# ENCE461TutorialSchematic.net
KiCad netlist of a schematic drawn in Altium Designer
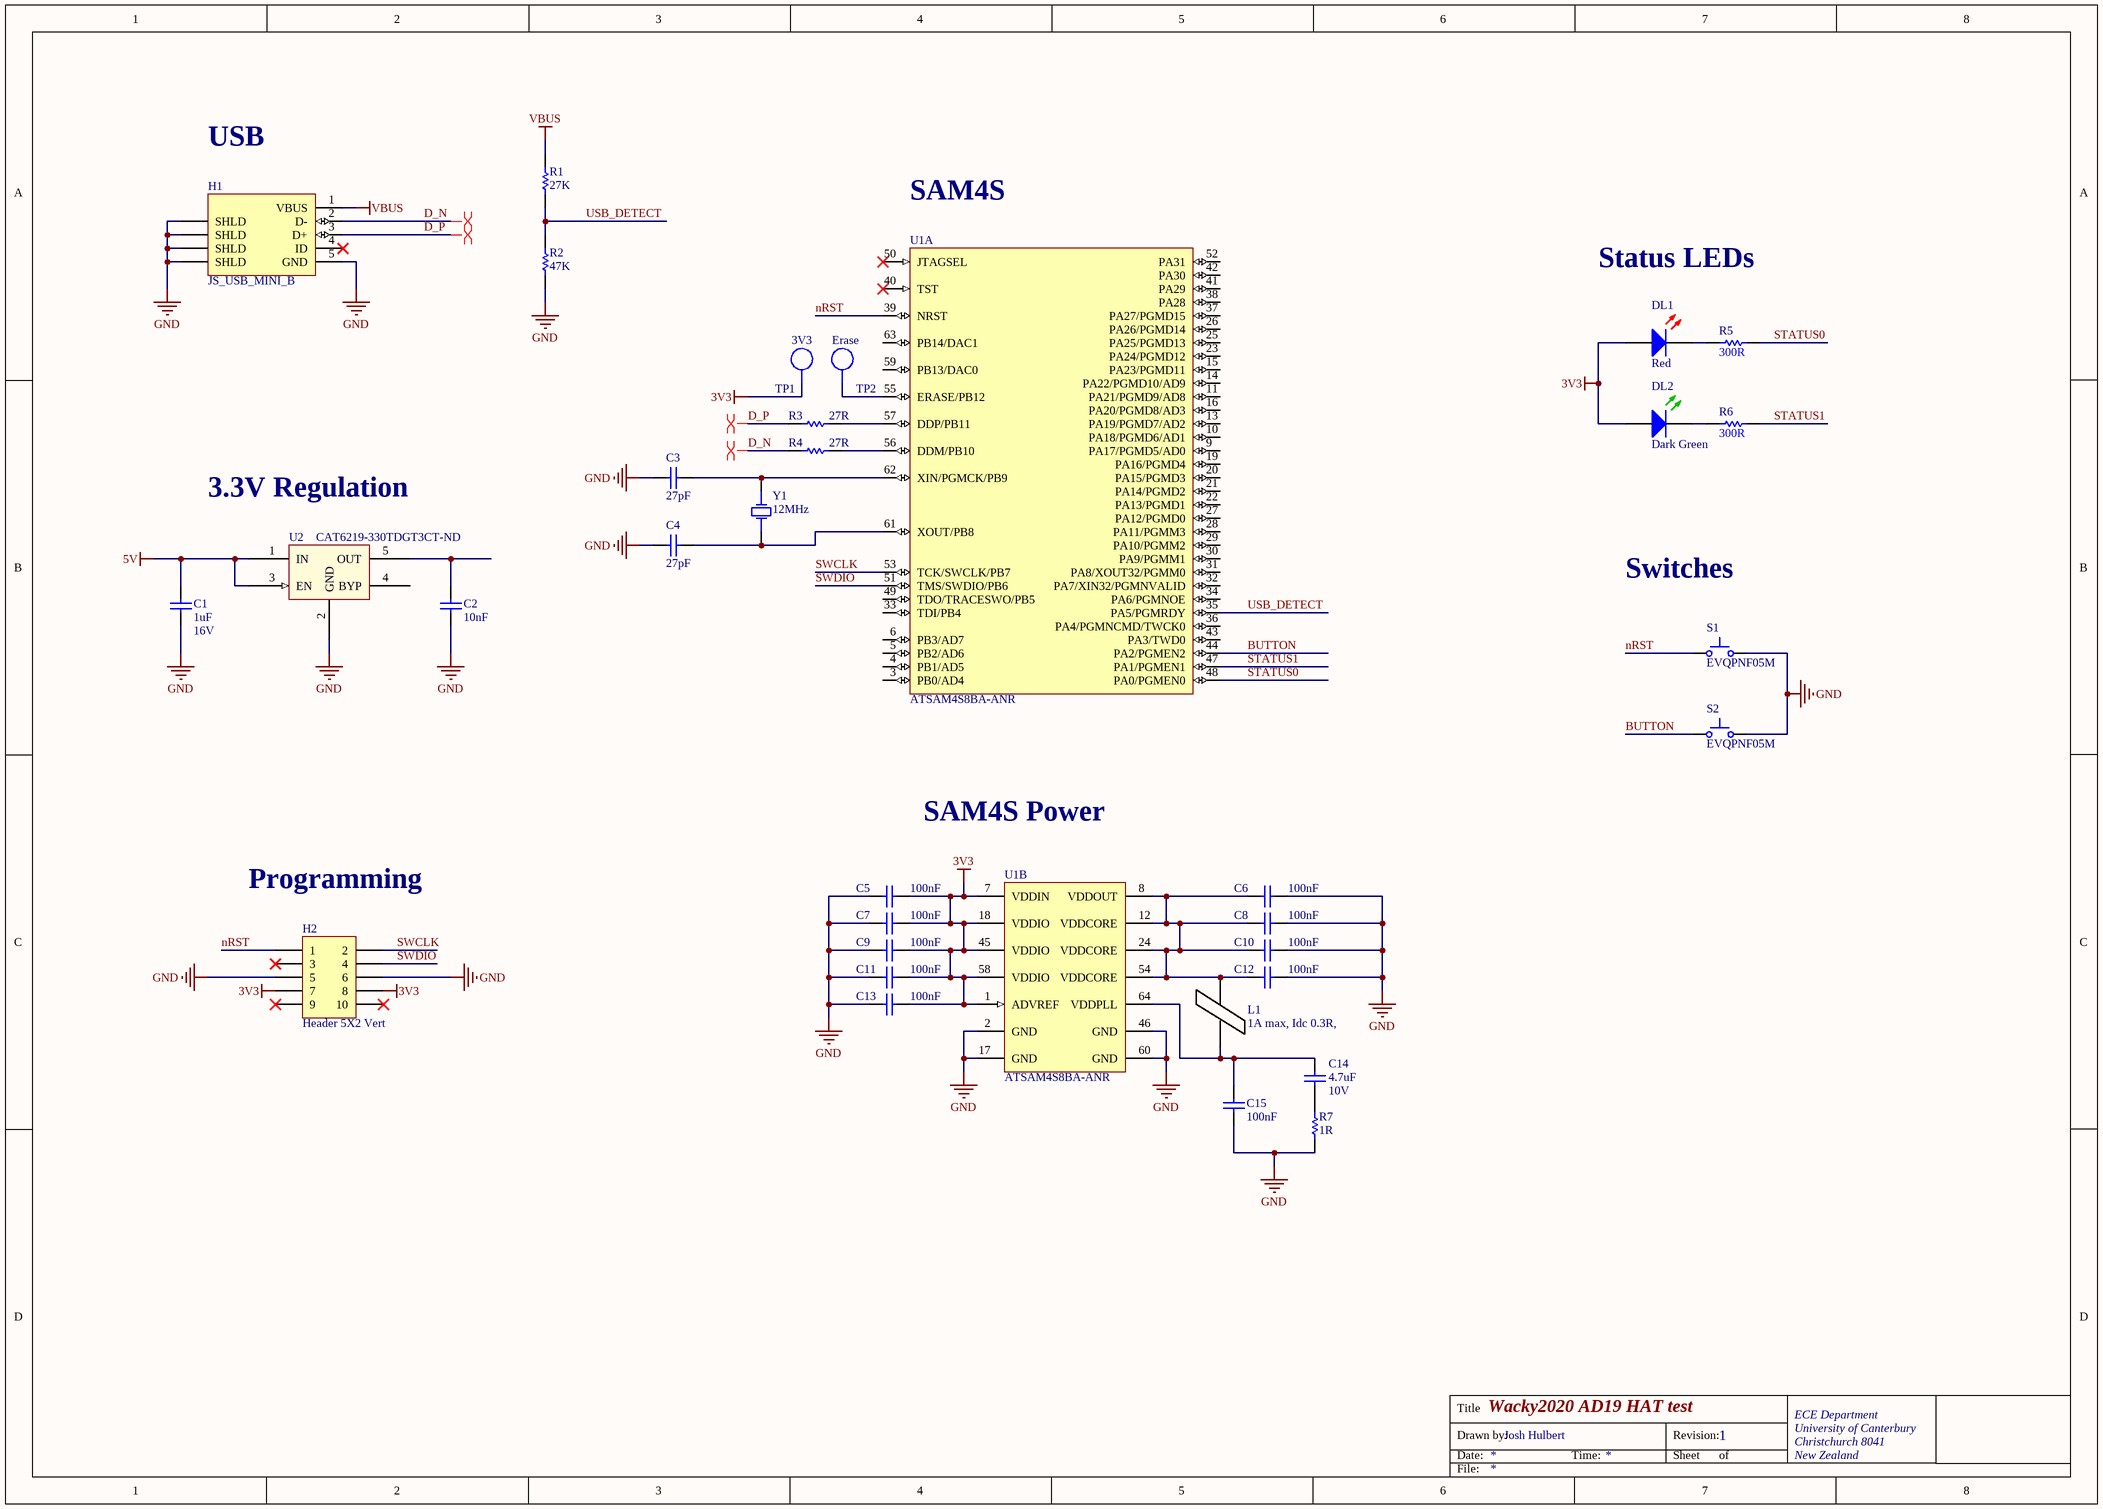
[diagram p0: ENCE461TutorialSchematic.SchDoc]

(export (version "E")
  (design (tool "Eeschema 10.0.6"))
  (components
    (comp (ref "C1")
      (value "1uF")
      (footprint "CAPC1608L")
      (description "CAP CER 1uF Y5V -20% +80% 16V 0603")
      (fields (field (name "MAX VOLTAGE") "16V"))
      (libsource (lib "ECE AD19Components_19V1") (part "CC_1uF_0603"))
    )
    (comp (ref "C2")
      (value "10nF")
      (footprint "CAPC1608L")
      (description "CAP CER 10nF X7R +-10% 50V 0603")
      (libsource (lib "ECE AD19Components_19V1") (part "CC_10nF_0603"))
    )
    (comp (ref "C3")
      (value "27pF")
      (footprint "CAPC1608L")
      (description "CAP CER 27pF NPO/COG +-5% 50V 0603")
      (libsource (lib "ECE AD19Components_19V1") (part "CC_27pF_0603"))
    )
    (comp (ref "C4")
      (value "27pF")
      (footprint "CAPC1608L")
      (description "CAP CER 27pF NPO/COG +-5% 50V 0603")
      (libsource (lib "ECE AD19Components_19V1") (part "CC_27pF_0603"))
    )
    (comp (ref "C5")
      (value "100nF")
      (footprint "CAPC1608L")
      (description "CAP CER 100nF X7R +-10% 50V 0603")
      (libsource (lib "ECE AD19Components_19V1") (part "CC_100nF_0603"))
    )
    (comp (ref "C6")
      (value "100nF")
      (footprint "CAPC1608L")
      (description "CAP CER 100nF X7R +-10% 50V 0603")
      (libsource (lib "ECE AD19Components_19V1") (part "CC_100nF_0603"))
    )
    (comp (ref "C7")
      (value "100nF")
      (footprint "CAPC1608L")
      (description "CAP CER 100nF X7R +-10% 50V 0603")
      (libsource (lib "ECE AD19Components_19V1") (part "CC_100nF_0603"))
    )
    (comp (ref "C8")
      (value "100nF")
      (footprint "CAPC1608L")
      (description "CAP CER 100nF X7R +-10% 50V 0603")
      (libsource (lib "ECE AD19Components_19V1") (part "CC_100nF_0603"))
    )
    (comp (ref "C9")
      (value "100nF")
      (footprint "CAPC1608L")
      (description "CAP CER 100nF X7R +-10% 50V 0603")
      (libsource (lib "ECE AD19Components_19V1") (part "CC_100nF_0603"))
    )
    (comp (ref "C10")
      (value "100nF")
      (footprint "CAPC1608L")
      (description "CAP CER 100nF X7R +-10% 50V 0603")
      (libsource (lib "ECE AD19Components_19V1") (part "CC_100nF_0603"))
    )
    (comp (ref "C11")
      (value "100nF")
      (footprint "CAPC1608L")
      (description "CAP CER 100nF X7R +-10% 50V 0603")
      (libsource (lib "ECE AD19Components_19V1") (part "CC_100nF_0603"))
    )
    (comp (ref "C12")
      (value "100nF")
      (footprint "CAPC1608L")
      (description "CAP CER 100nF X7R +-10% 50V 0603")
      (libsource (lib "ECE AD19Components_19V1") (part "CC_100nF_0603"))
    )
    (comp (ref "C13")
      (value "100nF")
      (footprint "CAPC1608L")
      (description "CAP CER 100nF X7R +-10% 50V 0603")
      (libsource (lib "ECE AD19Components_19V1") (part "CC_100nF_0603"))
    )
    (comp (ref "C14")
      (value "4.7uF")
      (footprint "CAPC1608N")
      (description "CAP CER 4.7uF X5R +-20%  10V 0603")
      (fields (field (name "MAX VOLTAGE") "10V"))
      (libsource (lib "ECE AD19Components_19V1") (part "CC_4.7uF_0603"))
    )
    (comp (ref "C15")
      (value "100nF")
      (footprint "CAPC1608L")
      (description "CAP CER 100nF X7R +-10% 50V 0603")
      (libsource (lib "ECE AD19Components_19V1") (part "CC_100nF_0603"))
    )
    (comp (ref "DL1")
      (value "Red")
      (footprint "WL-SMCW0603")
      (description "LED Red 250mcd 0603 SMD")
      (fields
        (field (name "MANUFACTURER") "WURTH ELEKTRONIK")
        (field (name "MANUFACTURER PART NUMBER") "150060RS75000")
        (field (name "LED COLOUR") "Red")
      )
      (libsource (lib "ECE AD19Components_19V1") (part "DL_150060RS75000"))
    )
    (comp (ref "DL2")
      (value "Dark Green")
      (footprint "WL-SMCW0603")
      (description "LED Dk Green 430mcd 0603 SMD")
      (fields
        (field (name "MANUFACTURER") "WURTH ELEKTRONIK")
        (field (name "MANUFACTURER PART NUMBER") "150060GS75000")
        (field (name "LED COLOUR") "Dark Green")
      )
      (libsource (lib "ECE AD19Components_19V1") (part "DL_150060GS75000"))
    )
    (comp (ref "H1")
      (value "JS_USB_MINI_B")
      (footprint "USB/SM0.8-6H5")
      (description "USB 2.0, Right Angle, SMT, B Type, Receptacle, 5 Position,")
      (fields (field (name "MANUFACTURER") "FCI"))
      (libsource (lib "ECE AD19Components_19V1") (part "JS_USB_MINI_B_SMT"))
    )
    (comp (ref "H2")
      (value "Header 5X2 Vert")
      (footprint "IDC2.54-V10D")
      (description "IDC Header, 2,54mm, 10-Pin, Vert")
      (libsource (lib "ECE AD19Components_19V1") (part "JA_HDR_IDC_5X2_VERT"))
    )
    (comp (ref "L1")
      (value "1A max, Idc 0.3R,")
      (footprint "INDC3216L")
      (description "Ferrite Bead, Rdc 0.3R, Z100MHZ 600R, Imax 1A, SMD 1206")
      (fields
        (field (name "MANUFACTURER") "FAIR-RITE")
        (field (name "MANUFACTURER PART NUMBER") "2512066017Y1")
      )
      (libsource (lib "ECE AD19Components_19V1") (part "IN_Ferrite-Bead"))
    )
    (comp (ref "R1")
      (value "27K")
      (footprint "RESC1608L")
      (description "RES 27K OHM 1/10W 5% 0603 SMD")
      (libsource (lib "ECE AD19Components_19V1") (part "RS_27K"))
    )
    (comp (ref "R2")
      (value "47K")
      (footprint "RESC1608N")
      (description "RES 47.0K OHM 1/10W 5% 0603 SMD")
      (libsource (lib "ECE AD19Components_19V1") (part "RS_47K"))
    )
    (comp (ref "R3")
      (value "27R")
      (footprint "RESC1608L")
      (description "RES 27 OHM 1/10W 5% 0603 SMD")
      (libsource (lib "ECE AD19Components_19V1") (part "RS_27R"))
    )
    (comp (ref "R4")
      (value "27R")
      (footprint "RESC1608L")
      (description "RES 27 OHM 1/10W 5% 0603 SMD")
      (libsource (lib "ECE AD19Components_19V1") (part "RS_27R"))
    )
    (comp (ref "R5")
      (value "300R")
      (footprint "RESC1608L")
      (description "RES 300 OHM 1/10W 5% 0603 SMD")
      (libsource (lib "ECE AD19Components_19V1") (part "RS_300R"))
    )
    (comp (ref "R6")
      (value "300R")
      (footprint "RESC1608L")
      (description "RES 300 OHM 1/10W 5% 0603 SMD")
      (libsource (lib "ECE AD19Components_19V1") (part "RS_300R"))
    )
    (comp (ref "R7")
      (value "1R")
      (footprint "RESC3216L")
      (description "RES 1R OHM 1/4W 5% 1206 SMD")
      (libsource (lib "ECE AD19Components_19V1") (part "RT_1R"))
    )
    (comp (ref "S1")
      (value "EVQPNF05M")
      (footprint "EVQPNF05M")
      (description "Panasonic 6 x 3.5mm SMD Light Touch Switch Type SMD")
      (fields (field (name "MANUFACTURER") "Panasonic"))
      (libsource (lib "ECE AD19Components_19V1") (part "WS_EVQPNF05M"))
    )
    (comp (ref "S2")
      (value "EVQPNF05M")
      (footprint "EVQPNF05M")
      (description "Panasonic 6 x 3.5mm SMD Light Touch Switch Type SMD")
      (fields (field (name "MANUFACTURER") "Panasonic"))
      (libsource (lib "ECE AD19Components_19V1") (part "WS_EVQPNF05M"))
    )
    (comp (ref "TP1")
      (value "3V3")
      (footprint "TP_1206")
      (description "Test-Point 3.3x1.6x2.1mm SMD")
      (fields
        (field (name "MANUFACTURER") "Harwin Inc")
        (field (name "MANUFACTURER PART NUMBER") "S1751-46R")
      )
      (libsource (lib "ECE AD19Components_19V1") (part "TP_1206"))
    )
    (comp (ref "TP2")
      (value "Erase")
      (footprint "TP_1206")
      (description "Test-Point 3.3x1.6x2.1mm SMD")
      (fields
        (field (name "MANUFACTURER") "Harwin Inc")
        (field (name "MANUFACTURER PART NUMBER") "S1751-46R")
      )
      (libsource (lib "ECE AD19Components_19V1") (part "TP_1206"))
    )
    (comp (ref "U1")
      (value "ATSAM4S8BA-ANR")
      (footprint "LQFP64_L")
      (description "IC MCU 32BIT 512KB FLASH 64LQFP")
      (fields (field (name "MANUFACTURER") "Atmel"))
      (libsource (lib "ECE AD19Components_19V1") (part "SE_ATSAM4S16BA-MU"))
    )
    (comp (ref "U2")
      (value "CAT6219-330TDGT3")
      (footprint "SOT95P280X145-5N")
      (description "IC REG LIN 3.3V 500MA TSOT23-5")
      (fields
        (field (name "BASE PART NUMBER") "CAT6219")
        (field (name "SUPPLIER PART NUMBER") "CAT6219-330TDGT3CT-ND")
      )
      (libsource (lib "ENCE461AD19_19V2") (part "SV_CAT6219-330TDGT3"))
    )
    (comp (ref "Y1")
      (value "12MHz")
      (footprint "6.0X3.5-4")
      (description "CRYSTAL 12MHZ 18PF 6X3.5mm SMD")
      (fields
        (field (name "MANUFACTURER") "CTS-Frequency Controls")
        (field (name "MANUFACTURER PART NUMBER") "406C35D12M00000")
        (field (name "FREQUENCY") "12MHz")
      )
      (libsource (lib "ECE AD19Components_19V1") (part "XT_CRYSTAL_12MHz_18pF"))
    )
  )
  (nets
    (net (code "1") (name "/BUTTON") (class "Default")
      (node (ref "S2") (pin "2") (pintype "passive"))
      (node (ref "U1") (pin "44") (pinfunction "PA2/PGMEN2_44") (pintype "bidirectional"))
    )
    (net (code "2") (name "/D_N") (class "Default")
      (node (ref "H1") (pin "2") (pinfunction "D-_2") (pintype "bidirectional"))
      (node (ref "R4") (pin "1") (pinfunction "1_1") (pintype "passive"))
    )
    (net (code "3") (name "/D_P") (class "Default")
      (node (ref "H1") (pin "3") (pinfunction "D+_3") (pintype "bidirectional"))
      (node (ref "R3") (pin "1") (pinfunction "1_1") (pintype "passive"))
    )
    (net (code "4") (name "/STATUS0") (class "Default")
      (node (ref "R5") (pin "2") (pinfunction "2_2") (pintype "passive"))
      (node (ref "U1") (pin "48") (pinfunction "PA0/PGMEN0_48") (pintype "bidirectional"))
    )
    (net (code "5") (name "/STATUS1") (class "Default")
      (node (ref "R6") (pin "2") (pinfunction "2_2") (pintype "passive"))
      (node (ref "U1") (pin "47") (pinfunction "PA1/PGMEN1_47") (pintype "bidirectional"))
    )
    (net (code "6") (name "/SWCLK") (class "Default")
      (node (ref "H2") (pin "2") (pinfunction "2_2") (pintype "passive"))
      (node (ref "U1") (pin "53") (pinfunction "TCK/SWCLK/PB7_53") (pintype "bidirectional"))
    )
    (net (code "7") (name "/SWDIO") (class "Default")
      (node (ref "H2") (pin "4") (pinfunction "4_4") (pintype "passive"))
      (node (ref "U1") (pin "51") (pinfunction "TMS/SWDIO/PB6_51") (pintype "bidirectional"))
    )
    (net (code "8") (name "/USB_DETECT") (class "Default")
      (node (ref "R1") (pin "1") (pinfunction "1_1") (pintype "passive"))
      (node (ref "R2") (pin "2") (pinfunction "2_2") (pintype "passive"))
      (node (ref "U1") (pin "35") (pinfunction "PA5/PGMRDY_35") (pintype "bidirectional"))
    )
    (net (code "9") (name "/nRST") (class "Default")
      (node (ref "H2") (pin "1") (pinfunction "1_1") (pintype "passive"))
      (node (ref "S1") (pin "2") (pintype "passive"))
      (node (ref "U1") (pin "39") (pinfunction "NRST_39") (pintype "bidirectional"))
    )
    (net (code "10") (name "3V3") (class "Default")
      (node (ref "C11") (pin "2") (pinfunction "2_2") (pintype "passive"))
      (node (ref "C13") (pin "2") (pinfunction "2_2") (pintype "passive"))
      (node (ref "C5") (pin "2") (pinfunction "2_2") (pintype "passive"))
      (node (ref "C7") (pin "2") (pinfunction "2_2") (pintype "passive"))
      (node (ref "C9") (pin "2") (pinfunction "2_2") (pintype "passive"))
      (node (ref "DL1") (pin "2") (pinfunction "A_2") (pintype "passive"))
      (node (ref "DL2") (pin "2") (pinfunction "A_2") (pintype "passive"))
      (node (ref "H2") (pin "7") (pinfunction "7_7") (pintype "passive"))
      (node (ref "H2") (pin "8") (pinfunction "8_8") (pintype "passive"))
      (node (ref "TP1") (pin "1") (pinfunction "1_1") (pintype "passive"))
      (node (ref "U1") (pin "1") (pinfunction "ADVREF_1") (pintype "input"))
      (node (ref "U1") (pin "18") (pinfunction "VDDIO_18") (pintype "power_in"))
      (node (ref "U1") (pin "45") (pinfunction "VDDIO_45") (pintype "power_in"))
      (node (ref "U1") (pin "58") (pinfunction "VDDIO_58") (pintype "power_in"))
      (node (ref "U1") (pin "7") (pinfunction "VDDIN_7") (pintype "power_in"))
    )
    (net (code "11") (name "5V") (class "Default")
      (node (ref "C1") (pin "2") (pinfunction "2_2") (pintype "passive"))
      (node (ref "U2") (pin "1") (pinfunction "IN_1") (pintype "power_in"))
      (node (ref "U2") (pin "3") (pinfunction "EN_3") (pintype "input"))
    )
    (net (code "12") (name "GND") (class "Default")
      (node (ref "C1") (pin "1") (pinfunction "1_1") (pintype "passive"))
      (node (ref "C10") (pin "2") (pinfunction "2_2") (pintype "passive"))
      (node (ref "C11") (pin "1") (pinfunction "1_1") (pintype "passive"))
      (node (ref "C12") (pin "2") (pinfunction "2_2") (pintype "passive"))
      (node (ref "C13") (pin "1") (pinfunction "1_1") (pintype "passive"))
      (node (ref "C15") (pin "2") (pinfunction "2_2") (pintype "passive"))
      (node (ref "C2") (pin "1") (pinfunction "1_1") (pintype "passive"))
      (node (ref "C3") (pin "1") (pinfunction "1_1") (pintype "passive"))
      (node (ref "C4") (pin "1") (pinfunction "1_1") (pintype "passive"))
      (node (ref "C5") (pin "1") (pinfunction "1_1") (pintype "passive"))
      (node (ref "C6") (pin "2") (pinfunction "2_2") (pintype "passive"))
      (node (ref "C7") (pin "1") (pinfunction "1_1") (pintype "passive"))
      (node (ref "C8") (pin "2") (pinfunction "2_2") (pintype "passive"))
      (node (ref "C9") (pin "1") (pinfunction "1_1") (pintype "passive"))
      (node (ref "H1") (pin "5") (pinfunction "GND_5") (pintype "passive"))
      (node (ref "H1") (pin "6") (pinfunction "SHLD_6") (pintype "passive"))
      (node (ref "H1") (pin "7") (pinfunction "SHLD_7") (pintype "passive"))
      (node (ref "H1") (pin "8") (pinfunction "SHLD_8") (pintype "passive"))
      (node (ref "H1") (pin "9") (pinfunction "SHLD_9") (pintype "passive"))
      (node (ref "H2") (pin "5") (pinfunction "5_5") (pintype "passive"))
      (node (ref "H2") (pin "6") (pinfunction "6_6") (pintype "passive"))
      (node (ref "R2") (pin "1") (pinfunction "1_1") (pintype "passive"))
      (node (ref "R7") (pin "1") (pinfunction "1_1") (pintype "passive"))
      (node (ref "S1") (pin "1") (pintype "passive"))
      (node (ref "S2") (pin "1") (pintype "passive"))
      (node (ref "U1") (pin "17") (pinfunction "GND_17") (pintype "power_in"))
      (node (ref "U1") (pin "2") (pinfunction "GND_2") (pintype "power_in"))
      (node (ref "U1") (pin "46") (pinfunction "GND_46") (pintype "power_in"))
      (node (ref "U1") (pin "60") (pinfunction "GND_60") (pintype "power_in"))
      (node (ref "U2") (pin "2") (pinfunction "GND_2") (pintype "power_in"))
    )
    (net (code "13") (name "Net-(C14-Pad1)") (class "Default")
      (node (ref "C14") (pin "1") (pinfunction "1_1") (pintype "passive"))
      (node (ref "R7") (pin "2") (pinfunction "2_2") (pintype "passive"))
    )
    (net (code "14") (name "Net-(DL1-K)") (class "Default")
      (node (ref "DL1") (pin "1") (pinfunction "K_1") (pintype "passive"))
      (node (ref "R5") (pin "1") (pinfunction "1_1") (pintype "passive"))
    )
    (net (code "15") (name "Net-(DL2-K)") (class "Default")
      (node (ref "DL2") (pin "1") (pinfunction "K_1") (pintype "passive"))
      (node (ref "R6") (pin "1") (pinfunction "1_1") (pintype "passive"))
    )
    (net (code "16") (name "Net-(U1A-DDM{slash}PB10)") (class "Default")
      (node (ref "R4") (pin "2") (pinfunction "2_2") (pintype "passive"))
      (node (ref "U1") (pin "56") (pinfunction "DDM/PB10_56") (pintype "bidirectional"))
    )
    (net (code "17") (name "Net-(U1A-DDP{slash}PB11)") (class "Default")
      (node (ref "R3") (pin "2") (pinfunction "2_2") (pintype "passive"))
      (node (ref "U1") (pin "57") (pinfunction "DDP/PB11_57") (pintype "bidirectional"))
    )
    (net (code "18") (name "Net-(U1A-ERASE{slash}PB12)") (class "Default")
      (node (ref "TP2") (pin "1") (pinfunction "1_1") (pintype "passive"))
      (node (ref "U1") (pin "55") (pinfunction "ERASE/PB12_55") (pintype "bidirectional"))
    )
    (net (code "19") (name "Net-(U1A-XIN{slash}PGMCK{slash}PB9)") (class "Default")
      (node (ref "C3") (pin "2") (pinfunction "2_2") (pintype "passive"))
      (node (ref "U1") (pin "62") (pinfunction "XIN/PGMCK/PB9_62") (pintype "bidirectional"))
      (node (ref "Y1") (pin "3") (pinfunction "OSC2_3") (pintype "passive"))
    )
    (net (code "20") (name "Net-(U1A-XOUT{slash}PB8)") (class "Default")
      (node (ref "C4") (pin "2") (pinfunction "2_2") (pintype "passive"))
      (node (ref "U1") (pin "61") (pinfunction "XOUT/PB8_61") (pintype "bidirectional"))
      (node (ref "Y1") (pin "1") (pinfunction "OSC1_1") (pintype "passive"))
    )
    (net (code "21") (name "Net-(U1B-VDDOUT)") (class "Default")
      (node (ref "C10") (pin "1") (pinfunction "1_1") (pintype "passive"))
      (node (ref "C12") (pin "1") (pinfunction "1_1") (pintype "passive"))
      (node (ref "C6") (pin "1") (pinfunction "1_1") (pintype "passive"))
      (node (ref "C8") (pin "1") (pinfunction "1_1") (pintype "passive"))
      (node (ref "L1") (pin "2") (pinfunction "2_2") (pintype "passive"))
      (node (ref "U1") (pin "12") (pinfunction "VDDCORE_12") (pintype "power_in"))
      (node (ref "U1") (pin "24") (pinfunction "VDDCORE_24") (pintype "power_in"))
      (node (ref "U1") (pin "54") (pinfunction "VDDCORE_54") (pintype "power_in"))
      (node (ref "U1") (pin "8") (pinfunction "VDDOUT_8") (pintype "power_in"))
    )
    (net (code "22") (name "Net-(U1B-VDDPLL)") (class "Default")
      (node (ref "C14") (pin "2") (pinfunction "2_2") (pintype "passive"))
      (node (ref "C15") (pin "1") (pinfunction "1_1") (pintype "passive"))
      (node (ref "L1") (pin "1") (pinfunction "1_1") (pintype "passive"))
      (node (ref "U1") (pin "64") (pinfunction "VDDPLL_64") (pintype "power_in"))
    )
    (net (code "23") (name "Net-(U2-OUT)") (class "Default")
      (node (ref "C2") (pin "2") (pinfunction "2_2") (pintype "passive"))
      (node (ref "U2") (pin "5") (pinfunction "OUT_5") (pintype "power_in"))
    )
    (net (code "24") (name "VBUS") (class "Default")
      (node (ref "H1") (pin "1") (pinfunction "VBUS_1") (pintype "power_in"))
      (node (ref "R1") (pin "2") (pinfunction "2_2") (pintype "passive"))
    )
    (net (code "25") (name "unconnected-(H1-ID-Pad4)") (class "Default")
      (node (ref "H1") (pin "4") (pinfunction "ID_4") (pintype "power_in+no_connect"))
    )
    (net (code "26") (name "unconnected-(H2-Pad3)") (class "Default")
      (node (ref "H2") (pin "3") (pinfunction "3_3") (pintype "passive+no_connect"))
    )
    (net (code "27") (name "unconnected-(H2-Pad9)") (class "Default")
      (node (ref "H2") (pin "9") (pinfunction "9_9") (pintype "passive+no_connect"))
    )
    (net (code "28") (name "unconnected-(H2-Pad10)") (class "Default")
      (node (ref "H2") (pin "10") (pinfunction "10_10") (pintype "passive+no_connect"))
    )
    (net (code "29") (name "unconnected-(U1A-JTAGSEL-Pad50)") (class "Default")
      (node (ref "U1") (pin "50") (pinfunction "JTAGSEL_50") (pintype "input+no_connect"))
    )
    (net (code "30") (name "unconnected-(U1A-PA3{slash}TWD0-Pad43)") (class "Default")
      (node (ref "U1") (pin "43") (pinfunction "PA3/TWD0_43") (pintype "bidirectional"))
    )
    (net (code "31") (name "unconnected-(U1A-PA4{slash}PGMNCMD{slash}TWCK0-Pad36)") (class "Default")
      (node (ref "U1") (pin "36") (pinfunction "PA4/PGMNCMD/TWCK0_36") (pintype "bidirectional"))
    )
    (net (code "32") (name "unconnected-(U1A-PA6{slash}PGMNOE-Pad34)") (class "Default")
      (node (ref "U1") (pin "34") (pinfunction "PA6/PGMNOE_34") (pintype "bidirectional"))
    )
    (net (code "33") (name "unconnected-(U1A-PA7{slash}XIN32{slash}PGMNVALID-Pad32)") (class "Default")
      (node (ref "U1") (pin "32") (pinfunction "PA7/XIN32/PGMNVALID_32") (pintype "bidirectional"))
    )
    (net (code "34") (name "unconnected-(U1A-PA8{slash}XOUT32{slash}PGMM0-Pad31)") (class "Default")
      (node (ref "U1") (pin "31") (pinfunction "PA8/XOUT32/PGMM0_31") (pintype "bidirectional"))
    )
    (net (code "35") (name "unconnected-(U1A-PA9{slash}PGMM1-Pad30)") (class "Default")
      (node (ref "U1") (pin "30") (pinfunction "PA9/PGMM1_30") (pintype "bidirectional"))
    )
    (net (code "36") (name "unconnected-(U1A-PA10{slash}PGMM2-Pad29)") (class "Default")
      (node (ref "U1") (pin "29") (pinfunction "PA10/PGMM2_29") (pintype "bidirectional"))
    )
    (net (code "37") (name "unconnected-(U1A-PA11{slash}PGMM3-Pad28)") (class "Default")
      (node (ref "U1") (pin "28") (pinfunction "PA11/PGMM3_28") (pintype "bidirectional"))
    )
    (net (code "38") (name "unconnected-(U1A-PA12{slash}PGMD0-Pad27)") (class "Default")
      (node (ref "U1") (pin "27") (pinfunction "PA12/PGMD0_27") (pintype "bidirectional"))
    )
    (net (code "39") (name "unconnected-(U1A-PA13{slash}PGMD1-Pad22)") (class "Default")
      (node (ref "U1") (pin "22") (pinfunction "PA13/PGMD1_22") (pintype "bidirectional"))
    )
    (net (code "40") (name "unconnected-(U1A-PA14{slash}PGMD2-Pad21)") (class "Default")
      (node (ref "U1") (pin "21") (pinfunction "PA14/PGMD2_21") (pintype "bidirectional"))
    )
    (net (code "41") (name "unconnected-(U1A-PA15{slash}PGMD3-Pad20)") (class "Default")
      (node (ref "U1") (pin "20") (pinfunction "PA15/PGMD3_20") (pintype "bidirectional"))
    )
    (net (code "42") (name "unconnected-(U1A-PA16{slash}PGMD4-Pad19)") (class "Default")
      (node (ref "U1") (pin "19") (pinfunction "PA16/PGMD4_19") (pintype "bidirectional"))
    )
    (net (code "43") (name "unconnected-(U1A-PA17{slash}PGMD5{slash}AD0-Pad9)") (class "Default")
      (node (ref "U1") (pin "9") (pinfunction "PA17/PGMD5/AD0_9") (pintype "bidirectional"))
    )
    (net (code "44") (name "unconnected-(U1A-PA18{slash}PGMD6{slash}AD1-Pad10)") (class "Default")
      (node (ref "U1") (pin "10") (pinfunction "PA18/PGMD6/AD1_10") (pintype "bidirectional"))
    )
    (net (code "45") (name "unconnected-(U1A-PA19{slash}PGMD7{slash}AD2-Pad13)") (class "Default")
      (node (ref "U1") (pin "13") (pinfunction "PA19/PGMD7/AD2_13") (pintype "bidirectional"))
    )
    (net (code "46") (name "unconnected-(U1A-PA20{slash}PGMD8{slash}AD3-Pad16)") (class "Default")
      (node (ref "U1") (pin "16") (pinfunction "PA20/PGMD8/AD3_16") (pintype "bidirectional"))
    )
    (net (code "47") (name "unconnected-(U1A-PA21{slash}PGMD9{slash}AD8-Pad11)") (class "Default")
      (node (ref "U1") (pin "11") (pinfunction "PA21/PGMD9/AD8_11") (pintype "bidirectional"))
    )
    (net (code "48") (name "unconnected-(U1A-PA22{slash}PGMD10{slash}AD9-Pad14)") (class "Default")
      (node (ref "U1") (pin "14") (pinfunction "PA22/PGMD10/AD9_14") (pintype "bidirectional"))
    )
    (net (code "49") (name "unconnected-(U1A-PA23{slash}PGMD11-Pad15)") (class "Default")
      (node (ref "U1") (pin "15") (pinfunction "PA23/PGMD11_15") (pintype "bidirectional"))
    )
    (net (code "50") (name "unconnected-(U1A-PA24{slash}PGMD12-Pad23)") (class "Default")
      (node (ref "U1") (pin "23") (pinfunction "PA24/PGMD12_23") (pintype "bidirectional"))
    )
    (net (code "51") (name "unconnected-(U1A-PA25{slash}PGMD13-Pad25)") (class "Default")
      (node (ref "U1") (pin "25") (pinfunction "PA25/PGMD13_25") (pintype "bidirectional"))
    )
    (net (code "52") (name "unconnected-(U1A-PA26{slash}PGMD14-Pad26)") (class "Default")
      (node (ref "U1") (pin "26") (pinfunction "PA26/PGMD14_26") (pintype "bidirectional"))
    )
    (net (code "53") (name "unconnected-(U1A-PA27{slash}PGMD15-Pad37)") (class "Default")
      (node (ref "U1") (pin "37") (pinfunction "PA27/PGMD15_37") (pintype "bidirectional"))
    )
    (net (code "54") (name "unconnected-(U1A-PA28-Pad38)") (class "Default")
      (node (ref "U1") (pin "38") (pinfunction "PA28_38") (pintype "bidirectional"))
    )
    (net (code "55") (name "unconnected-(U1A-PA29-Pad41)") (class "Default")
      (node (ref "U1") (pin "41") (pinfunction "PA29_41") (pintype "bidirectional"))
    )
    (net (code "56") (name "unconnected-(U1A-PA30-Pad42)") (class "Default")
      (node (ref "U1") (pin "42") (pinfunction "PA30_42") (pintype "bidirectional"))
    )
    (net (code "57") (name "unconnected-(U1A-PA31-Pad52)") (class "Default")
      (node (ref "U1") (pin "52") (pinfunction "PA31_52") (pintype "bidirectional"))
    )
    (net (code "58") (name "unconnected-(U1A-PB0{slash}AD4-Pad3)") (class "Default")
      (node (ref "U1") (pin "3") (pinfunction "PB0/AD4_3") (pintype "bidirectional"))
    )
    (net (code "59") (name "unconnected-(U1A-PB1{slash}AD5-Pad4)") (class "Default")
      (node (ref "U1") (pin "4") (pinfunction "PB1/AD5_4") (pintype "bidirectional"))
    )
    (net (code "60") (name "unconnected-(U1A-PB2{slash}AD6-Pad5)") (class "Default")
      (node (ref "U1") (pin "5") (pinfunction "PB2/AD6_5") (pintype "bidirectional"))
    )
    (net (code "61") (name "unconnected-(U1A-PB3{slash}AD7-Pad6)") (class "Default")
      (node (ref "U1") (pin "6") (pinfunction "PB3/AD7_6") (pintype "bidirectional"))
    )
    (net (code "62") (name "unconnected-(U1A-PB13{slash}DAC0-Pad59)") (class "Default")
      (node (ref "U1") (pin "59") (pinfunction "PB13/DAC0_59") (pintype "bidirectional"))
    )
    (net (code "63") (name "unconnected-(U1A-PB14{slash}DAC1-Pad63)") (class "Default")
      (node (ref "U1") (pin "63") (pinfunction "PB14/DAC1_63") (pintype "bidirectional"))
    )
    (net (code "64") (name "unconnected-(U1A-TDI{slash}PB4-Pad33)") (class "Default")
      (node (ref "U1") (pin "33") (pinfunction "TDI/PB4_33") (pintype "bidirectional"))
    )
    (net (code "65") (name "unconnected-(U1A-TDO{slash}TRACESWO{slash}PB5-Pad49)") (class "Default")
      (node (ref "U1") (pin "49") (pinfunction "TDO/TRACESWO/PB5_49") (pintype "bidirectional"))
    )
    (net (code "66") (name "unconnected-(U1A-TST-Pad40)") (class "Default")
      (node (ref "U1") (pin "40") (pinfunction "TST_40") (pintype "input+no_connect"))
    )
    (net (code "67") (name "unconnected-(U2-BYP-Pad4)") (class "Default")
      (node (ref "U2") (pin "4") (pinfunction "BYP_4") (pintype "passive"))
    )
  )
)
